# Sheet1.net
KiCad netlist of a schematic drawn in Altium Designer
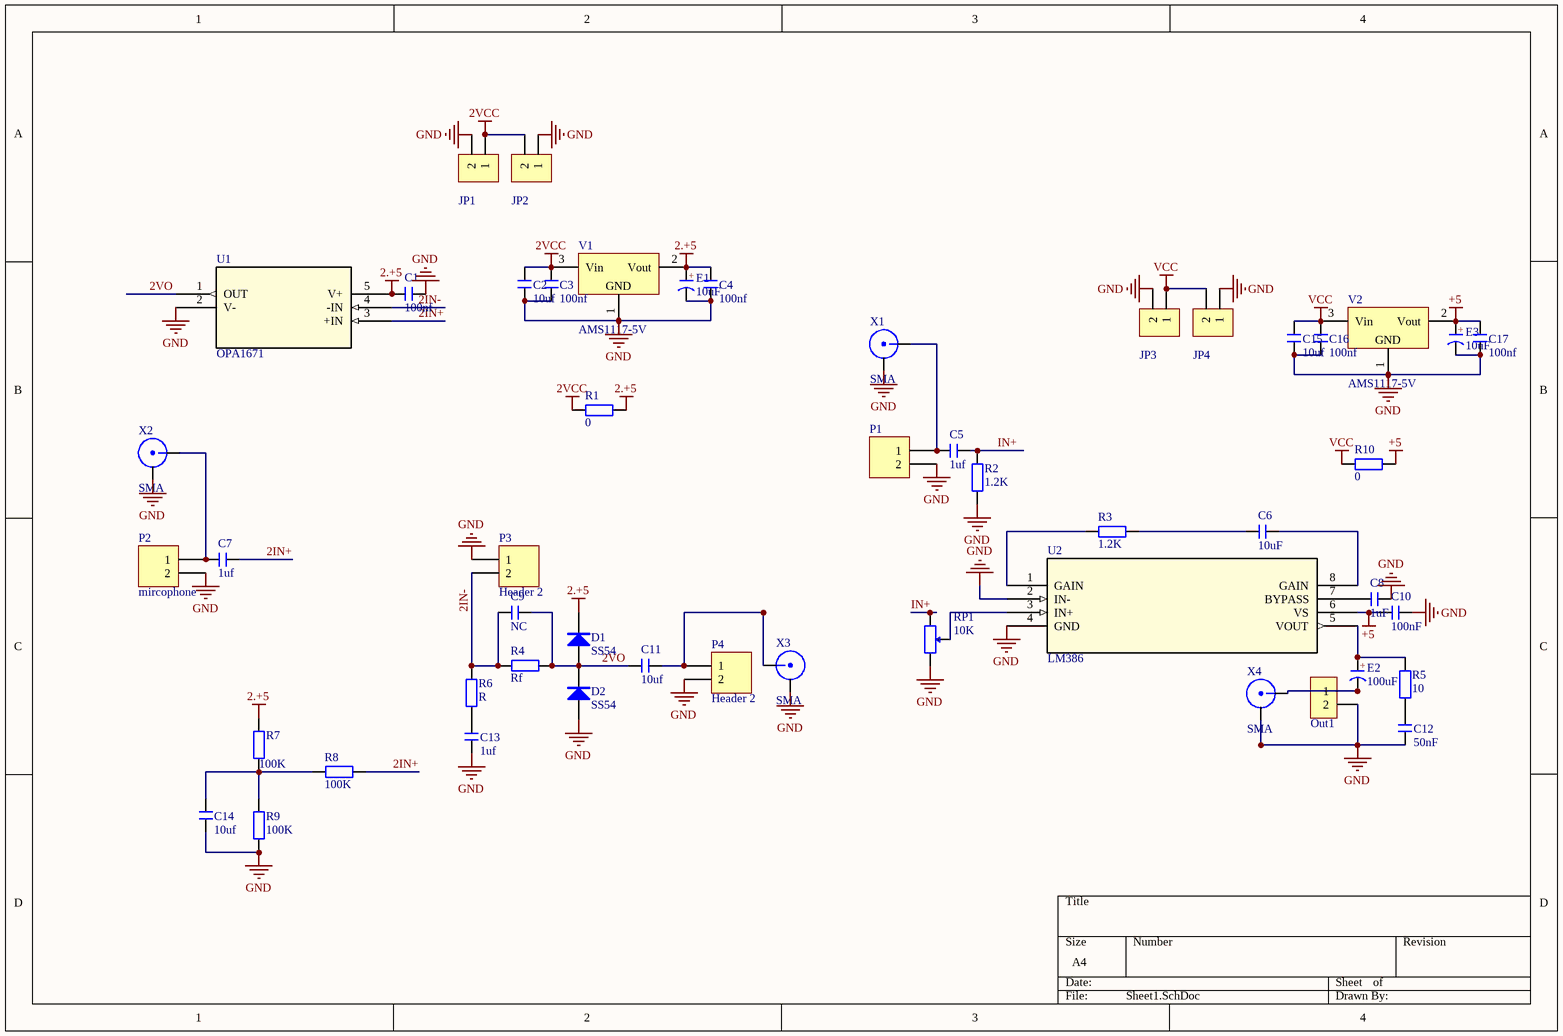
[diagram p0: Sheet1.SchDoc]

(export (version "E")
  (design (tool "Eeschema 10.0.6"))
  (components
    (comp (ref "C1")
      (value "100nf")
      (footprint "C 0603_L")
      (description "无极性贴片电容")
      (fields (field (name "版权归属") "源创客"))
      (libsource (lib "IL") (part "C"))
    )
    (comp (ref "C2")
      (value "10uf")
      (footprint "C 0603_L")
      (description "无极性贴片电容")
      (fields (field (name "版权归属") "源创客"))
      (libsource (lib "IL") (part "C"))
    )
    (comp (ref "C3")
      (value "100nf")
      (footprint "C 0603_L")
      (description "无极性贴片电容")
      (fields (field (name "版权归属") "源创客"))
      (libsource (lib "IL") (part "C"))
    )
    (comp (ref "C4")
      (value "100nf")
      (footprint "C 0603_L")
      (description "无极性贴片电容")
      (fields (field (name "版权归属") "源创客"))
      (libsource (lib "IL") (part "C"))
    )
    (comp (ref "C5")
      (value "1uf")
      (footprint "C 0603_L")
      (description "无极性贴片电容")
      (fields (field (name "版权归属") "源创客"))
      (libsource (lib "IL") (part "C"))
    )
    (comp (ref "C6")
      (value "10uF")
      (footprint "C 0603_L")
      (description "无极性贴片电容")
      (fields (field (name "版权归属") "源创客"))
      (libsource (lib "IL") (part "C"))
    )
    (comp (ref "C7")
      (value "1uf")
      (footprint "C 0603_L")
      (description "无极性贴片电容")
      (fields (field (name "版权归属") "源创客"))
      (libsource (lib "IL") (part "C"))
    )
    (comp (ref "C8")
      (value "1uF")
      (footprint "C 0603_L")
      (description "无极性贴片电容")
      (fields (field (name "版权归属") "源创客"))
      (libsource (lib "IL") (part "C"))
    )
    (comp (ref "C9")
      (value "NC")
      (footprint "C 0603_L")
      (description "无极性贴片电容")
      (fields (field (name "版权归属") "源创客"))
      (libsource (lib "IL") (part "C"))
    )
    (comp (ref "C10")
      (value "100nF")
      (footprint "C 0603_L")
      (description "无极性贴片电容")
      (fields (field (name "版权归属") "源创客"))
      (libsource (lib "IL") (part "C"))
    )
    (comp (ref "C11")
      (value "10uf")
      (footprint "C 0603_L")
      (description "无极性贴片电容")
      (fields (field (name "版权归属") "源创客"))
      (libsource (lib "IL") (part "C"))
    )
    (comp (ref "C12")
      (value "50nF")
      (footprint "C 0603_L")
      (description "无极性贴片电容")
      (fields (field (name "版权归属") "源创客"))
      (libsource (lib "IL") (part "C"))
    )
    (comp (ref "C13")
      (value "1uf")
      (footprint "C 0603_L")
      (description "无极性贴片电容")
      (fields (field (name "版权归属") "源创客"))
      (libsource (lib "IL") (part "C"))
    )
    (comp (ref "C14")
      (value "10uf")
      (footprint "C 0603_L")
      (description "无极性贴片电容")
      (fields (field (name "版权归属") "源创客"))
      (libsource (lib "IL") (part "C"))
    )
    (comp (ref "C15")
      (value "10uf")
      (footprint "C 0603_L")
      (description "无极性贴片电容")
      (fields (field (name "版权归属") "源创客"))
      (libsource (lib "IL") (part "C"))
    )
    (comp (ref "C16")
      (value "100nf")
      (footprint "C 0603_L")
      (description "无极性贴片电容")
      (fields (field (name "版权归属") "源创客"))
      (libsource (lib "IL") (part "C"))
    )
    (comp (ref "C17")
      (value "100nf")
      (footprint "C 0603_L")
      (description "无极性贴片电容")
      (fields (field (name "版权归属") "源创客"))
      (libsource (lib "IL") (part "C"))
    )
    (comp (ref "D1")
      (value "SS54")
      (footprint "SMA")
      (description "肖特基二极管")
      (fields (field (name "版权归属") "源创客"))
      (libsource (lib "IL") (part "SR540"))
    )
    (comp (ref "D2")
      (value "SS54")
      (footprint "SMA")
      (description "肖特基二极管")
      (fields (field (name "版权归属") "源创客"))
      (libsource (lib "IL") (part "SR540"))
    )
    (comp (ref "E1")
      (value "10uF")
      (footprint "CD B(3528)")
      (description "贴片钽电容")
      (fields (field (name "版权归属") "源创客"))
      (libsource (lib "IL") (part "C-CD"))
    )
    (comp (ref "E2")
      (value "100uF")
      (footprint "CAP 2.5*6.3*7")
      (description "直插电解电容")
      (fields (field (name "版权归属") "源创客"))
      (libsource (lib "IL") (part "C-CAP"))
    )
    (comp (ref "E3")
      (value "10uF")
      (footprint "CD B(3528)")
      (description "贴片钽电容")
      (fields (field (name "版权归属") "源创客"))
      (libsource (lib "IL") (part "C-CD"))
    )
    (comp (ref "JP1")
      (value "HDR-1X2")
      (footprint "VH3.96-LI-2P")
      (description "2P接插件")
      (fields (field (name "版权归属") "源创客"))
      (libsource (lib "IL") (part "Header 2_1"))
    )
    (comp (ref "JP2")
      (value "HDR-1X2")
      (footprint "VH3.96-LI-2P")
      (description "2P接插件")
      (fields (field (name "版权归属") "源创客"))
      (libsource (lib "IL") (part "Header 2_1"))
    )
    (comp (ref "JP3")
      (value "HDR-1X2")
      (footprint "VH3.96-LI-2P")
      (description "2P接插件")
      (fields (field (name "版权归属") "源创客"))
      (libsource (lib "IL") (part "Header 2_1"))
    )
    (comp (ref "JP4")
      (value "HDR-1X2")
      (footprint "VH3.96-LI-2P")
      (description "2P接插件")
      (fields (field (name "版权归属") "源创客"))
      (libsource (lib "IL") (part "Header 2_1"))
    )
    (comp (ref "Out1")
      (value "HDR-1X2")
      (footprint "HDR2.54-LI-2P")
      (description "2P接插件")
      (fields (field (name "版权归属") "源创客"))
      (libsource (lib "IL") (part "Header 2"))
    )
    (comp (ref "P1")
      (value "~")
      (footprint "HDR1X2")
      (description "Header, 2-Pin")
      (fields (field (name "PUBLISHER") "Altium Limited"))
      (libsource (lib "Miscellaneous Connectors") (part "Header 2"))
    )
    (comp (ref "P2")
      (value "mircophone")
      (footprint "HDR1X2")
      (description "Header, 2-Pin")
      (fields (field (name "PUBLISHER") "Altium Limited"))
      (libsource (lib "Miscellaneous Connectors") (part "Header 2"))
    )
    (comp (ref "P3")
      (value "Header 2")
      (footprint "HDR1X2")
      (description "Header, 2-Pin")
      (fields (field (name "PUBLISHER") "Altium Limited"))
      (libsource (lib "") (part "Header 2_1"))
    )
    (comp (ref "P4")
      (value "Header 2")
      (footprint "HDR1X2")
      (description "Header, 2-Pin")
      (fields (field (name "PUBLISHER") "Altium Limited"))
      (libsource (lib "") (part "Header 2_1"))
    )
    (comp (ref "R1")
      (value "0")
      (footprint "R 0603_L")
      (description "贴片电阻")
      (fields (field (name "版权归属") "源创客"))
      (libsource (lib "IL") (part "R"))
    )
    (comp (ref "R2")
      (value "1.2K")
      (footprint "R 0603_L")
      (description "贴片电阻")
      (fields (field (name "版权归属") "源创客"))
      (libsource (lib "IL") (part "R"))
    )
    (comp (ref "R3")
      (value "1.2K")
      (footprint "R 0603_L")
      (description "贴片电阻")
      (fields (field (name "版权归属") "源创客"))
      (libsource (lib "IL") (part "R"))
    )
    (comp (ref "R4")
      (value "Rf")
      (footprint "R 0603_L")
      (description "贴片电阻")
      (fields (field (name "版权归属") "源创客"))
      (libsource (lib "IL") (part "R"))
    )
    (comp (ref "R5")
      (value "10")
      (footprint "R 0603_L")
      (description "贴片电阻")
      (fields (field (name "版权归属") "源创客"))
      (libsource (lib "IL") (part "R"))
    )
    (comp (ref "R6")
      (value "R")
      (footprint "R 0603_L")
      (description "贴片电阻")
      (fields (field (name "版权归属") "源创客"))
      (libsource (lib "IL") (part "R"))
    )
    (comp (ref "R7")
      (value "100K")
      (footprint "R 0603_L")
      (description "贴片电阻")
      (fields (field (name "版权归属") "源创客"))
      (libsource (lib "IL") (part "R"))
    )
    (comp (ref "R8")
      (value "100K")
      (footprint "R 0603_L")
      (description "贴片电阻")
      (fields (field (name "版权归属") "源创客"))
      (libsource (lib "IL") (part "R"))
    )
    (comp (ref "R9")
      (value "100K")
      (footprint "R 0603_L")
      (description "贴片电阻")
      (fields (field (name "版权归属") "源创客"))
      (libsource (lib "IL") (part "R"))
    )
    (comp (ref "R10")
      (value "0")
      (footprint "R 0603_L")
      (description "贴片电阻")
      (fields (field (name "版权归属") "源创客"))
      (libsource (lib "IL") (part "R"))
    )
    (comp (ref "RP1")
      (value "10K")
      (footprint "3296W")
      (description "插件单联电位器")
      (fields (field (name "版权归属") "源创客"))
      (libsource (lib "IL") (part "RP-ID"))
    )
    (comp (ref "U1")
      (value "OPA1671")
      (footprint "SOT23-DBV5_TEX")
      (description "低噪声音频运算放大器")
      (fields
        (field (name "MANUFACTURER_PART_NUMBER") "OPA1671IDBVR")
        (field (name "COPYRIGHT") "Copyright (C) 2021 Ultra Librarian. All rights reserved.")
      )
      (libsource (lib "IL") (part "OPA1671IDBVR"))
    )
    (comp (ref "U2")
      (value "LM386")
      (footprint "SOP8_L")
      (description "700mW音频功放")
      (fields
        (field (name "MANUFACTURER_PART_NUMBER") "LM386M-1/NOPB")
        (field (name "COPYRIGHT") "Copyright (C) 2021 Ultra Librarian. All rights reserved.")
      )
      (libsource (lib "IL") (part "LM386"))
    )
    (comp (ref "V1")
      (value "AMS1117-5V")
      (footprint "SOT223_L")
      (description "三端稳压芯片")
      (fields (field (name "版权归属") "源创客"))
      (libsource (lib "IL") (part "AMS1117"))
    )
    (comp (ref "V2")
      (value "AMS1117-5V")
      (footprint "SOT223_L")
      (description "三端稳压芯片")
      (fields (field (name "版权归属") "源创客"))
      (libsource (lib "IL") (part "AMS1117"))
    )
    (comp (ref "X1") (value "SMA") (footprint "SMA1") (libsource (lib "Library") (part "SMA")))
    (comp (ref "X2") (value "SMA") (footprint "SMA1") (libsource (lib "Library") (part "SMA")))
    (comp (ref "X3") (value "SMA") (footprint "SMA1") (libsource (lib "") (part "SMA_1")))
    (comp (ref "X4") (value "SMA") (footprint "SMA1") (libsource (lib "Library") (part "SMA")))
  )
  (nets
    (net (code "1") (name "+5") (class "Default")
      (node (ref "C10") (pin "1") (pinfunction "1_1") (pintype "passive"))
      (node (ref "C17") (pin "2") (pinfunction "2_2") (pintype "passive"))
      (node (ref "E3") (pin "1") (pinfunction "A_1") (pintype "passive"))
      (node (ref "R10") (pin "2") (pinfunction "2_2") (pintype "passive"))
      (node (ref "U2") (pin "6") (pinfunction "VS_6") (pintype "power_in"))
      (node (ref "V2") (pin "2") (pinfunction "Vout_2") (pintype "passive"))
    )
    (net (code "2") (name "/2IN+") (class "Default")
      (node (ref "C7") (pin "1") (pinfunction "1_1") (pintype "passive"))
      (node (ref "R8") (pin "2") (pinfunction "2_2") (pintype "passive"))
      (node (ref "U1") (pin "3") (pinfunction "+IN_3") (pintype "input"))
    )
    (net (code "3") (name "/2IN-") (class "Default")
      (node (ref "C9") (pin "2") (pinfunction "2_2") (pintype "passive"))
      (node (ref "P3") (pin "2") (pinfunction "2_2") (pintype "passive"))
      (node (ref "R4") (pin "2") (pinfunction "2_2") (pintype "passive"))
      (node (ref "R6") (pin "2") (pinfunction "2_2") (pintype "passive"))
      (node (ref "U1") (pin "4") (pinfunction "-IN_4") (pintype "input"))
    )
    (net (code "4") (name "/2VO") (class "Default")
      (node (ref "C11") (pin "2") (pinfunction "2_2") (pintype "passive"))
      (node (ref "C9") (pin "1") (pinfunction "1_1") (pintype "passive"))
      (node (ref "D1") (pin "1") (pinfunction "A_1") (pintype "passive"))
      (node (ref "D2") (pin "2") (pinfunction "K_2") (pintype "passive"))
      (node (ref "R4") (pin "1") (pinfunction "1_1") (pintype "passive"))
      (node (ref "U1") (pin "1") (pinfunction "OUT_1") (pintype "output"))
    )
    (net (code "5") (name "/IN+") (class "Default")
      (node (ref "C5") (pin "1") (pinfunction "1_1") (pintype "passive"))
      (node (ref "R2") (pin "2") (pinfunction "2_2") (pintype "passive"))
      (node (ref "RP1") (pin "1") (pinfunction "1_1") (pintype "passive"))
    )
    (net (code "6") (name "2.+5") (class "Default")
      (node (ref "C1") (pin "2") (pinfunction "2_2") (pintype "passive"))
      (node (ref "C4") (pin "2") (pinfunction "2_2") (pintype "passive"))
      (node (ref "D1") (pin "2") (pinfunction "K_2") (pintype "passive"))
      (node (ref "E1") (pin "1") (pinfunction "A_1") (pintype "passive"))
      (node (ref "R1") (pin "2") (pinfunction "2_2") (pintype "passive"))
      (node (ref "R7") (pin "2") (pinfunction "2_2") (pintype "passive"))
      (node (ref "U1") (pin "5") (pinfunction "V+_5") (pintype "power_in"))
      (node (ref "V1") (pin "2") (pinfunction "Vout_2") (pintype "passive"))
    )
    (net (code "7") (name "2VCC") (class "Default")
      (node (ref "C2") (pin "2") (pinfunction "2_2") (pintype "passive"))
      (node (ref "C3") (pin "2") (pinfunction "2_2") (pintype "passive"))
      (node (ref "JP1") (pin "1") (pinfunction "1_1") (pintype "passive"))
      (node (ref "JP2") (pin "2") (pinfunction "2_2") (pintype "passive"))
      (node (ref "R1") (pin "1") (pinfunction "1_1") (pintype "passive"))
      (node (ref "V1") (pin "3") (pinfunction "Vin_3") (pintype "passive"))
    )
    (net (code "8") (name "GND") (class "Default")
      (node (ref "C1") (pin "1") (pinfunction "1_1") (pintype "passive"))
      (node (ref "C10") (pin "2") (pinfunction "2_2") (pintype "passive"))
      (node (ref "C12") (pin "1") (pinfunction "1_1") (pintype "passive"))
      (node (ref "C13") (pin "1") (pinfunction "1_1") (pintype "passive"))
      (node (ref "C14") (pin "2") (pinfunction "2_2") (pintype "passive"))
      (node (ref "C15") (pin "1") (pinfunction "1_1") (pintype "passive"))
      (node (ref "C16") (pin "1") (pinfunction "1_1") (pintype "passive"))
      (node (ref "C17") (pin "1") (pinfunction "1_1") (pintype "passive"))
      (node (ref "C2") (pin "1") (pinfunction "1_1") (pintype "passive"))
      (node (ref "C3") (pin "1") (pinfunction "1_1") (pintype "passive"))
      (node (ref "C4") (pin "1") (pinfunction "1_1") (pintype "passive"))
      (node (ref "C8") (pin "2") (pinfunction "2_2") (pintype "passive"))
      (node (ref "D2") (pin "1") (pinfunction "A_1") (pintype "passive"))
      (node (ref "E1") (pin "2") (pinfunction "K_2") (pintype "passive"))
      (node (ref "E3") (pin "2") (pinfunction "K_2") (pintype "passive"))
      (node (ref "JP1") (pin "2") (pinfunction "2_2") (pintype "passive"))
      (node (ref "JP2") (pin "1") (pinfunction "1_1") (pintype "passive"))
      (node (ref "JP3") (pin "2") (pinfunction "2_2") (pintype "passive"))
      (node (ref "JP4") (pin "1") (pinfunction "1_1") (pintype "passive"))
      (node (ref "Out1") (pin "2") (pinfunction "2_2") (pintype "passive"))
      (node (ref "P1") (pin "2") (pinfunction "2_2") (pintype "passive"))
      (node (ref "P2") (pin "2") (pinfunction "2_2") (pintype "passive"))
      (node (ref "P3") (pin "1") (pinfunction "1_1") (pintype "passive"))
      (node (ref "P4") (pin "2") (pinfunction "2_2") (pintype "passive"))
      (node (ref "R2") (pin "1") (pinfunction "1_1") (pintype "passive"))
      (node (ref "R9") (pin "1") (pinfunction "1_1") (pintype "passive"))
      (node (ref "RP1") (pin "3") (pinfunction "3_3") (pintype "passive"))
      (node (ref "U1") (pin "2") (pinfunction "V-_2") (pintype "power_in"))
      (node (ref "U2") (pin "2") (pinfunction "IN-_2") (pintype "input"))
      (node (ref "U2") (pin "4") (pinfunction "GND_4") (pintype "power_in"))
      (node (ref "V1") (pin "1") (pinfunction "GND_1") (pintype "passive"))
      (node (ref "V2") (pin "1") (pinfunction "GND_1") (pintype "passive"))
      (node (ref "X1") (pin "2") (pinfunction "2_2") (pintype "passive"))
      (node (ref "X2") (pin "2") (pinfunction "2_2") (pintype "passive"))
      (node (ref "X3") (pin "2") (pinfunction "2_2") (pintype "passive"))
      (node (ref "X4") (pin "2") (pinfunction "2_2") (pintype "passive"))
    )
    (net (code "9") (name "Net-(C5-Pad2)") (class "Default")
      (node (ref "C5") (pin "2") (pinfunction "2_2") (pintype "passive"))
      (node (ref "P1") (pin "1") (pinfunction "1_1") (pintype "passive"))
      (node (ref "X1") (pin "1") (pinfunction "1_1") (pintype "passive"))
    )
    (net (code "10") (name "Net-(C6-Pad1)") (class "Default")
      (node (ref "C6") (pin "1") (pinfunction "1_1") (pintype "passive"))
      (node (ref "R3") (pin "2") (pinfunction "2_2") (pintype "passive"))
    )
    (net (code "11") (name "Net-(C6-Pad2)") (class "Default")
      (node (ref "C6") (pin "2") (pinfunction "2_2") (pintype "passive"))
      (node (ref "U2") (pin "8") (pinfunction "GAIN_8") (pintype "passive"))
    )
    (net (code "12") (name "Net-(C7-Pad2)") (class "Default")
      (node (ref "C7") (pin "2") (pinfunction "2_2") (pintype "passive"))
      (node (ref "P2") (pin "1") (pinfunction "1_1") (pintype "passive"))
      (node (ref "X2") (pin "1") (pinfunction "1_1") (pintype "passive"))
    )
    (net (code "13") (name "Net-(C11-Pad1)") (class "Default")
      (node (ref "C11") (pin "1") (pinfunction "1_1") (pintype "passive"))
      (node (ref "P4") (pin "1") (pinfunction "1_1") (pintype "passive"))
      (node (ref "X3") (pin "1") (pinfunction "1_1") (pintype "passive"))
    )
    (net (code "14") (name "Net-(C12-Pad2)") (class "Default")
      (node (ref "C12") (pin "2") (pinfunction "2_2") (pintype "passive"))
      (node (ref "R5") (pin "1") (pinfunction "1_1") (pintype "passive"))
    )
    (net (code "15") (name "Net-(C13-Pad2)") (class "Default")
      (node (ref "C13") (pin "2") (pinfunction "2_2") (pintype "passive"))
      (node (ref "R6") (pin "1") (pinfunction "1_1") (pintype "passive"))
    )
    (net (code "16") (name "Net-(C14-Pad1)") (class "Default")
      (node (ref "C14") (pin "1") (pinfunction "1_1") (pintype "passive"))
      (node (ref "R7") (pin "1") (pinfunction "1_1") (pintype "passive"))
      (node (ref "R8") (pin "1") (pinfunction "1_1") (pintype "passive"))
      (node (ref "R9") (pin "2") (pinfunction "2_2") (pintype "passive"))
    )
    (net (code "17") (name "Net-(E2-A)") (class "Default")
      (node (ref "E2") (pin "1") (pinfunction "A_1") (pintype "passive"))
      (node (ref "R5") (pin "2") (pinfunction "2_2") (pintype "passive"))
      (node (ref "U2") (pin "5") (pinfunction "VOUT_5") (pintype "output"))
    )
    (net (code "18") (name "Net-(E2-K)") (class "Default")
      (node (ref "E2") (pin "2") (pinfunction "K_2") (pintype "passive"))
      (node (ref "Out1") (pin "1") (pinfunction "1_1") (pintype "passive"))
      (node (ref "X4") (pin "1") (pinfunction "1_1") (pintype "passive"))
    )
    (net (code "19") (name "Net-(R3-Pad1)") (class "Default")
      (node (ref "R3") (pin "1") (pinfunction "1_1") (pintype "passive"))
      (node (ref "U2") (pin "1") (pinfunction "GAIN_1") (pintype "passive"))
    )
    (net (code "20") (name "Net-(U2-BYPASS)") (class "Default")
      (node (ref "C8") (pin "1") (pinfunction "1_1") (pintype "passive"))
      (node (ref "U2") (pin "7") (pinfunction "BYPASS_7") (pintype "passive"))
    )
    (net (code "21") (name "Net-(U2-IN+)") (class "Default")
      (node (ref "RP1") (pin "2") (pinfunction "2_2") (pintype "passive"))
      (node (ref "U2") (pin "3") (pinfunction "IN+_3") (pintype "input"))
    )
    (net (code "22") (name "VCC") (class "Default")
      (node (ref "C15") (pin "2") (pinfunction "2_2") (pintype "passive"))
      (node (ref "C16") (pin "2") (pinfunction "2_2") (pintype "passive"))
      (node (ref "JP3") (pin "1") (pinfunction "1_1") (pintype "passive"))
      (node (ref "JP4") (pin "2") (pinfunction "2_2") (pintype "passive"))
      (node (ref "R10") (pin "1") (pinfunction "1_1") (pintype "passive"))
      (node (ref "V2") (pin "3") (pinfunction "Vin_3") (pintype "passive"))
    )
  )
)
